# TPS5430.net
KiCad netlist of a schematic drawn in Altium Designer
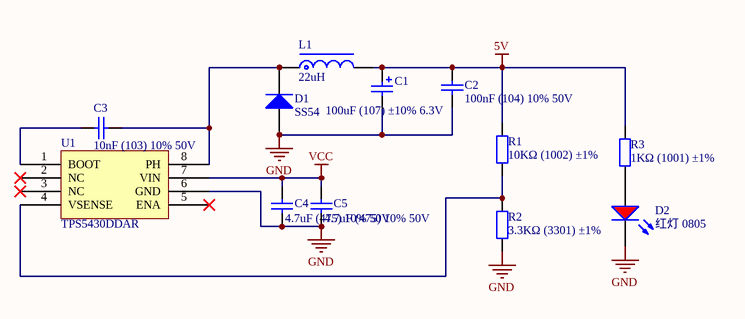
[diagram p0: TPS5430.SchDoc]

(export (version "E")
  (design (tool "Eeschema 10.0.6"))
  (components
    (comp (ref "C1")
      (value "100uF (107) ±10% 6.3V")
      (footprint "LC-CASE-B_3528")
      (description "钽电容")
      (libsource (lib "Miscellaneous Devices LC") (part "3528 100uF (107) 10% 6.3V"))
    )
    (comp (ref "C2")
      (value "100nF (104) 10% 50V")
      (footprint "LC-0603_C")
      (description "贴片电容")
      (libsource (lib "Miscellaneous Devices LC") (part "0603 100nF (104) 10% 50V"))
    )
    (comp (ref "C3")
      (value "10nF (103) 10% 50V")
      (footprint "LC-0603_C")
      (description "贴片电容")
      (libsource (lib "Miscellaneous Devices LC") (part "0603 10nF (103) 10% 50V"))
    )
    (comp (ref "C4")
      (value "4.7uF (475) 10% 50V")
      (footprint "LC-1206_C")
      (description "贴片电容")
      (libsource (lib "Miscellaneous Devices LC") (part "1206 4.7uF (475) 10% 50V"))
    )
    (comp (ref "C5")
      (value "4.7uF (475) 10% 50V")
      (footprint "LC-1206_C")
      (description "贴片电容")
      (libsource (lib "Miscellaneous Devices LC") (part "1206 4.7uF (475) 10% 50V"))
    )
    (comp (ref "D1")
      (value "SS54")
      (footprint "LC-SMA(DO-214AC)_S1")
      (description "二极管")
      (libsource (lib "Miscellaneous Devices LC") (part "SMA(DO-214AC) SS54"))
    )
    (comp (ref "D2")
      (value "红灯 0805")
      (footprint "LC-0805_LED_S1")
      (description "发光二极管")
      (libsource (lib "Miscellaneous Devices LC") (part "0805 红灯"))
    )
    (comp (ref "L1")
      (value "22uH")
      (footprint "CD54")
      (description "贴片功率电感")
      (fields (field (name "版权归属") "源创客"))
      (libsource (lib "3.1   - 电阻-电容-电感") (part "L-CD"))
    )
    (comp (ref "R1")
      (value "10KΩ (1002) ±1%")
      (footprint "LC-0805_R")
      (description "贴片电阻")
      (libsource (lib "Miscellaneous Devices LC") (part "0805 10KΩ (1002) 1%"))
    )
    (comp (ref "R2")
      (value "3.3KΩ (3301) ±1%")
      (footprint "LC-0805_R")
      (description "贴片电阻")
      (libsource (lib "Miscellaneous Devices LC") (part "0805 3.3KΩ (3301) 1%"))
    )
    (comp (ref "R3")
      (value "1KΩ (1001) ±1%")
      (footprint "LC-0805_R")
      (description "贴片电阻")
      (libsource (lib "Miscellaneous Devices LC") (part "0805 1KΩ (1001) 1%"))
    )
    (comp (ref "U1")
      (value "TPS5430DDAR")
      (footprint "LC-SOP-8_EP_150mil")
      (description "DC-DC芯片")
      (libsource (lib "Miscellaneous Devices LC") (part "TPS5430DDAR"))
    )
  )
  (nets
    (net (code "1") (name "5V") (class "Default")
      (node (ref "C1") (pin "1") (pinfunction "1_1") (pintype "passive"))
      (node (ref "C2") (pin "2") (pinfunction "2_2") (pintype "passive"))
      (node (ref "L1") (pin "2") (pinfunction "2_2") (pintype "passive"))
      (node (ref "R1") (pin "2") (pinfunction "2_2") (pintype "passive"))
      (node (ref "R3") (pin "2") (pinfunction "2_2") (pintype "passive"))
    )
    (net (code "2") (name "GND") (class "Default")
      (node (ref "C1") (pin "2") (pinfunction "2_2") (pintype "passive"))
      (node (ref "C2") (pin "1") (pinfunction "1_1") (pintype "passive"))
      (node (ref "C4") (pin "1") (pinfunction "1_1") (pintype "passive"))
      (node (ref "C5") (pin "1") (pinfunction "1_1") (pintype "passive"))
      (node (ref "D1") (pin "1") (pinfunction "A_1") (pintype "passive"))
      (node (ref "D2") (pin "K") (pinfunction "K_K") (pintype "passive"))
      (node (ref "R2") (pin "1") (pinfunction "1_1") (pintype "passive"))
      (node (ref "U1") (pin "6") (pinfunction "GND_6") (pintype "passive"))
    )
    (net (code "3") (name "Net-(D1-K)") (class "Default")
      (node (ref "C3") (pin "2") (pinfunction "2_2") (pintype "passive"))
      (node (ref "D1") (pin "2") (pinfunction "K_2") (pintype "passive"))
      (node (ref "L1") (pin "1") (pinfunction "1_1") (pintype "passive"))
      (node (ref "U1") (pin "8") (pinfunction "PH_8") (pintype "passive"))
    )
    (net (code "4") (name "Net-(D2-PadA)") (class "Default")
      (node (ref "D2") (pin "A") (pinfunction "A_A") (pintype "passive"))
      (node (ref "R3") (pin "1") (pinfunction "1_1") (pintype "passive"))
    )
    (net (code "5") (name "Net-(U1-BOOT)") (class "Default")
      (node (ref "C3") (pin "1") (pinfunction "1_1") (pintype "passive"))
      (node (ref "U1") (pin "1") (pinfunction "BOOT_1") (pintype "passive"))
    )
    (net (code "6") (name "Net-(U1-VSENSE)") (class "Default")
      (node (ref "R1") (pin "1") (pinfunction "1_1") (pintype "passive"))
      (node (ref "R2") (pin "2") (pinfunction "2_2") (pintype "passive"))
      (node (ref "U1") (pin "4") (pinfunction "VSENSE_4") (pintype "passive"))
    )
    (net (code "7") (name "VCC") (class "Default")
      (node (ref "C4") (pin "2") (pinfunction "2_2") (pintype "passive"))
      (node (ref "C5") (pin "2") (pinfunction "2_2") (pintype "passive"))
      (node (ref "U1") (pin "7") (pinfunction "VIN_7") (pintype "passive"))
    )
    (net (code "8") (name "unconnected-(U1-ENA-Pad5)") (class "Default")
      (node (ref "U1") (pin "5") (pinfunction "ENA_5") (pintype "passive+no_connect"))
    )
    (net (code "9") (name "unconnected-(U1-NC-Pad2)") (class "Default")
      (node (ref "U1") (pin "2") (pinfunction "NC_2") (pintype "passive+no_connect"))
    )
    (net (code "10") (name "unconnected-(U1-NC-Pad3)") (class "Default")
      (node (ref "U1") (pin "3") (pinfunction "NC_3") (pintype "passive+no_connect"))
    )
  )
)
